# 1P3W_v1p4.net
KiCad netlist of a schematic drawn in EAGLE
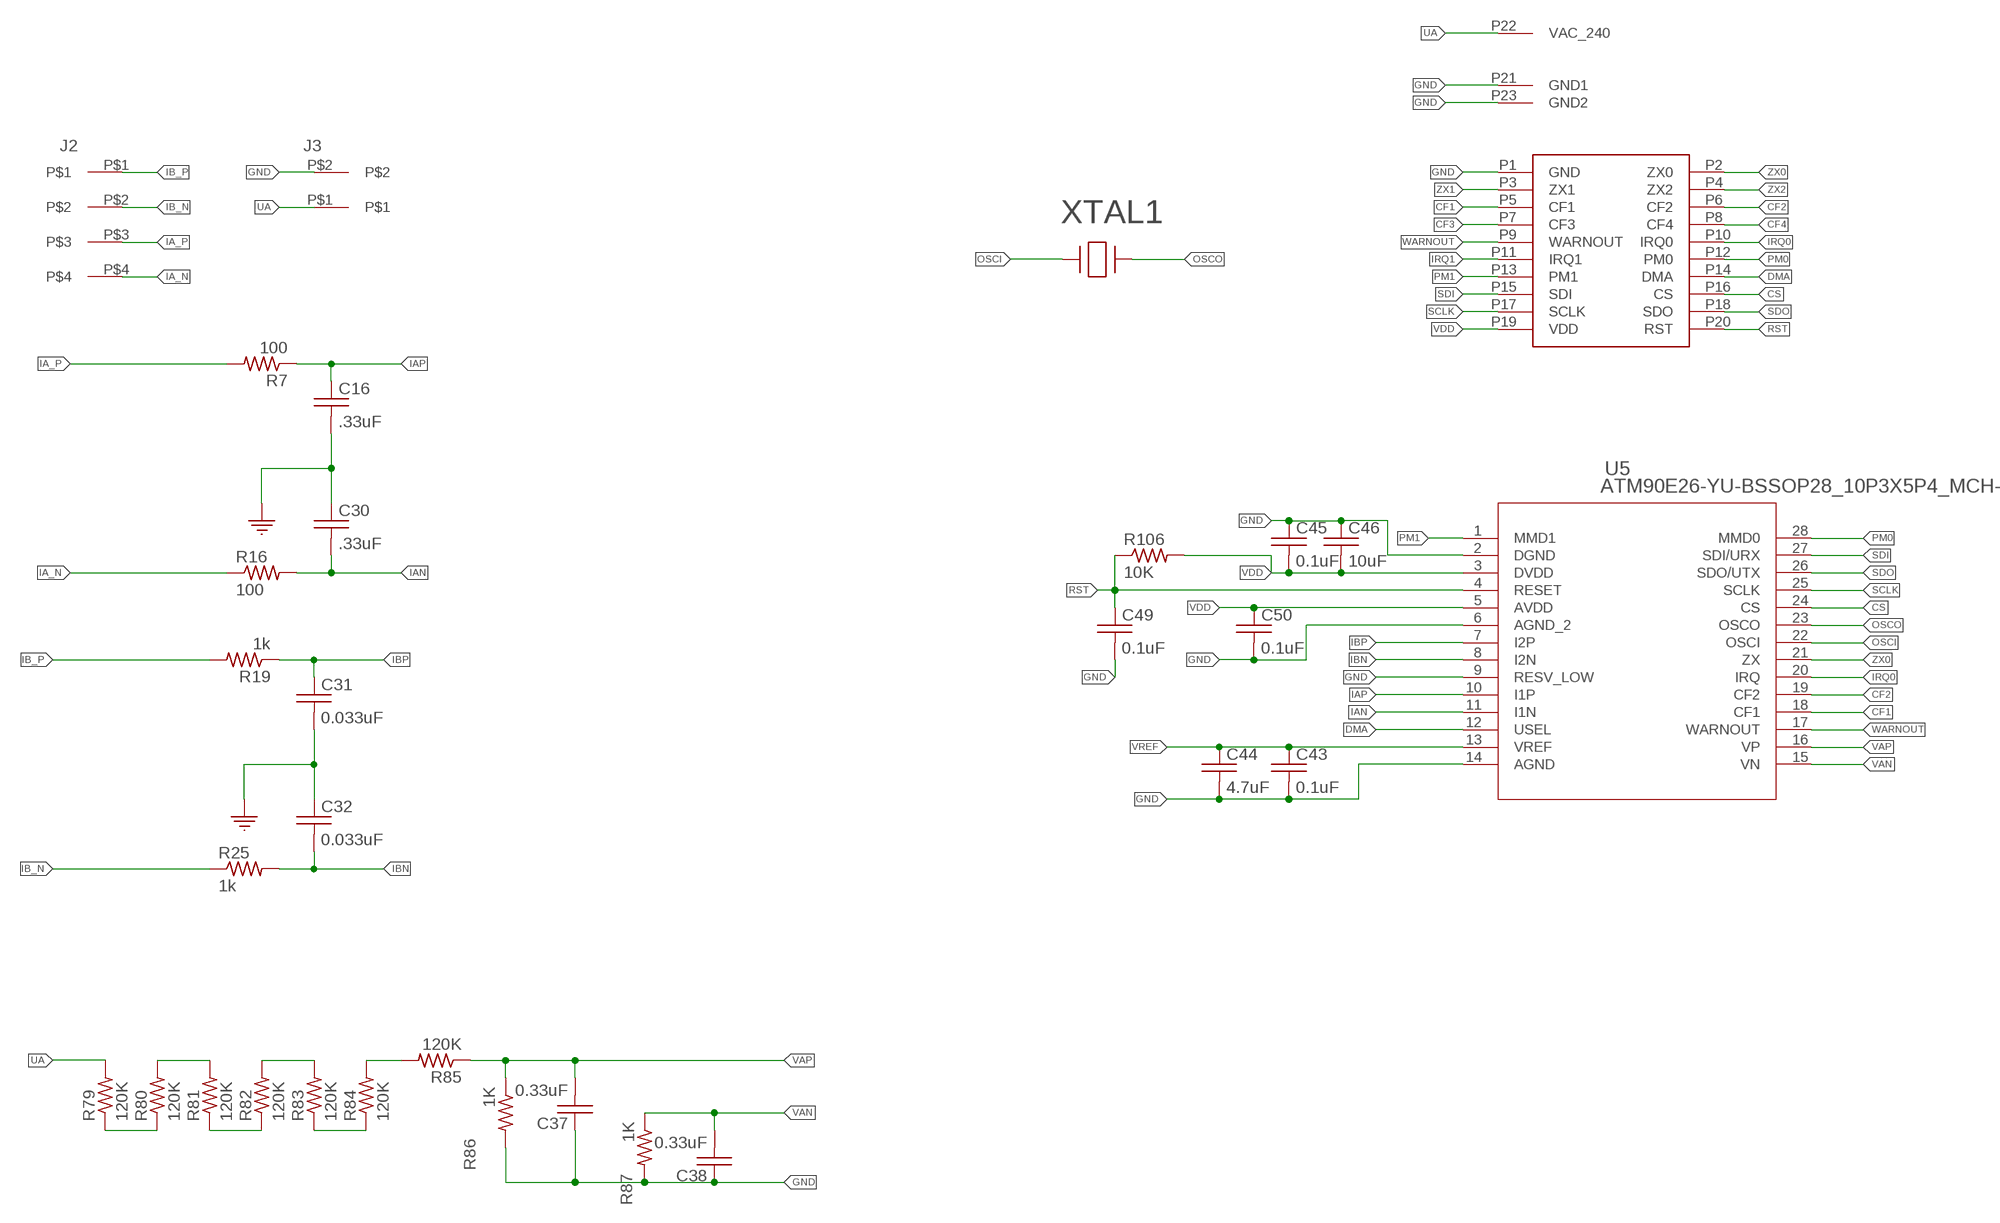
[diagram p0: schematic, sheet 1]

(export (version "E")
  (design (tool "Eeschema 10.0.6"))
  (components
    (comp (ref "C16")
      (value ".33uF")
      (footprint "eagle-import:0402")
      (libsource (lib "eagle-import") (part "C_0402"))
    )
    (comp (ref "C30")
      (value ".33uF")
      (footprint "eagle-import:0402")
      (libsource (lib "eagle-import") (part "C_0402"))
    )
    (comp (ref "C31")
      (value "0.033uF")
      (footprint "eagle-import:0402")
      (libsource (lib "eagle-import") (part "C_0402"))
    )
    (comp (ref "C32")
      (value "0.033uF")
      (footprint "eagle-import:0402")
      (libsource (lib "eagle-import") (part "C_0402"))
    )
    (comp (ref "C37")
      (value "0.33uF")
      (footprint "eagle-import:0402")
      (libsource (lib "eagle-import") (part "C_0402"))
    )
    (comp (ref "C38")
      (value "0.33uF")
      (footprint "eagle-import:0402")
      (libsource (lib "eagle-import") (part "C_0402"))
    )
    (comp (ref "C43")
      (value "0.1uF")
      (footprint "eagle-import:0402")
      (libsource (lib "eagle-import") (part "C_0402"))
    )
    (comp (ref "C44")
      (value "4.7uF")
      (footprint "eagle-import:0402")
      (libsource (lib "eagle-import") (part "C_0402"))
    )
    (comp (ref "C45")
      (value "0.1uF")
      (footprint "eagle-import:0402")
      (libsource (lib "eagle-import") (part "C_0402"))
    )
    (comp (ref "C46")
      (value "10uF")
      (footprint "eagle-import:0402")
      (libsource (lib "eagle-import") (part "C_0402"))
    )
    (comp (ref "C49")
      (value "0.1uF")
      (footprint "eagle-import:0402")
      (libsource (lib "eagle-import") (part "C_0402"))
    )
    (comp (ref "C50")
      (value "0.1uF")
      (footprint "eagle-import:0402")
      (libsource (lib "eagle-import") (part "C_0402"))
    )
    (comp (ref "J2")
      (value "3.81MM_1_X_4_RT_ANGLE_PLUG_HEADER")
      (footprint "eagle-import:1X4_3.81MM_PITCH")
      (libsource (lib "eagle-import") (part "3.81MM_1_X_4_RT_ANGLE_PLUG_HEADER"))
    )
    (comp (ref "J3")
      (value "3.81MM_1_X_2_RT_ANGLE_PLUG_HEADER")
      (footprint "eagle-import:2_3.81MM_PITCH")
      (libsource (lib "eagle-import") (part "3.81MM_1_X_2_RT_ANGLE_PLUG_HEADER"))
    )
    (comp (ref "R7")
      (value "100")
      (footprint "eagle-import:0402")
      (libsource (lib "eagle-import") (part "R_0402"))
    )
    (comp (ref "R16")
      (value "100")
      (footprint "eagle-import:0402")
      (libsource (lib "eagle-import") (part "R_0402"))
    )
    (comp (ref "R19")
      (value "1k")
      (footprint "eagle-import:0402")
      (libsource (lib "eagle-import") (part "R_0402"))
    )
    (comp (ref "R25")
      (value "1k")
      (footprint "eagle-import:0402")
      (libsource (lib "eagle-import") (part "R_0402"))
    )
    (comp (ref "R79")
      (value "120K")
      (footprint "eagle-import:0402")
      (libsource (lib "eagle-import") (part "R_0402"))
    )
    (comp (ref "R80")
      (value "120K")
      (footprint "eagle-import:0402")
      (libsource (lib "eagle-import") (part "R_0402"))
    )
    (comp (ref "R81")
      (value "120K")
      (footprint "eagle-import:0402")
      (libsource (lib "eagle-import") (part "R_0402"))
    )
    (comp (ref "R82")
      (value "120K")
      (footprint "eagle-import:0402")
      (libsource (lib "eagle-import") (part "R_0402"))
    )
    (comp (ref "R83")
      (value "120K")
      (footprint "eagle-import:0402")
      (libsource (lib "eagle-import") (part "R_0402"))
    )
    (comp (ref "R84")
      (value "120K")
      (footprint "eagle-import:0402")
      (libsource (lib "eagle-import") (part "R_0402"))
    )
    (comp (ref "R85")
      (value "120K")
      (footprint "eagle-import:0402")
      (libsource (lib "eagle-import") (part "R_0402"))
    )
    (comp (ref "R86")
      (value "1K")
      (footprint "eagle-import:0402")
      (libsource (lib "eagle-import") (part "R_0402"))
    )
    (comp (ref "R87")
      (value "1K")
      (footprint "eagle-import:0402")
      (libsource (lib "eagle-import") (part "R_0402"))
    )
    (comp (ref "R106")
      (value "10K")
      (footprint "eagle-import:0402")
      (libsource (lib "eagle-import") (part "R_0402"))
    )
    (comp (ref "U$1")
      (value "METER_BASE")
      (footprint "eagle-import:METER_BASE")
      (libsource (lib "eagle-import") (part "METER_BASE"))
    )
    (comp (ref "U5")
      (value "ATM90E26-YU-BSSOP28_10P3X5P4_MCH-M")
      (footprint "eagle-import:SSOP28_10P3X5P4_MCH-M")
      (fields
        (field (name "MANUFACTURER_PART_NUMBER") "ATM90E26-YU-B")
        (field (name "COPYRIGHT") "Copyright (C) 2018 Accelerated Designs. All rights reserved")
      )
      (libsource (lib "eagle-import") (part "ATM90E26-YU-BSSOP28_10P3X5P4_MCH-M"))
    )
    (comp (ref "XTAL1")
      (value "ABLS-8.192MHZ-B2-TXTAL_HC/49US_ABLS_ABR-M")
      (footprint "eagle-import:XTAL_HC_49US_ABLS_ABR-M")
      (fields
        (field (name "MANUFACTURER_PART_NUMBER") "ABLS-8.192MHZ-B2-T")
        (field (name "COPYRIGHT") "Copyright (C) 2018 Accelerated Designs. All rights reserved")
      )
      (libsource (lib "eagle-import") (part "ABLS-8.192MHZ-B2-TXTAL_HC/49US_ABLS_ABR-M"))
    )
  )
  (nets
    (net (code "1") (name "CF1") (class "Default")
      (node (ref "U$1") (pin "P5") (pinfunction "CF1_P5") (pintype "bidirectional"))
      (node (ref "U5") (pin "18") (pinfunction "CF1_18") (pintype "bidirectional"))
    )
    (net (code "2") (name "CF2") (class "Default")
      (node (ref "U$1") (pin "P6") (pinfunction "CF2_P6") (pintype "bidirectional"))
      (node (ref "U5") (pin "19") (pinfunction "CF2_19") (pintype "bidirectional"))
    )
    (net (code "3") (name "CF3") (class "Default")
      (node (ref "U$1") (pin "P7") (pinfunction "CF3_P7") (pintype "bidirectional"))
    )
    (net (code "4") (name "CF4") (class "Default")
      (node (ref "U$1") (pin "P8") (pinfunction "CF4_P8") (pintype "bidirectional"))
    )
    (net (code "5") (name "CS") (class "Default")
      (node (ref "U$1") (pin "P16") (pinfunction "CS_P16") (pintype "bidirectional"))
      (node (ref "U5") (pin "24") (pinfunction "CS_24") (pintype "passive"))
    )
    (net (code "6") (name "DMA") (class "Default")
      (node (ref "U$1") (pin "P14") (pinfunction "DMA_P14") (pintype "bidirectional"))
      (node (ref "U5") (pin "12") (pinfunction "USEL_12") (pintype "passive"))
    )
    (net (code "7") (name "GND") (class "Default")
      (node (ref "C16") (pin "P$2") (pinfunction "2_P$2") (pintype "passive"))
      (node (ref "C30") (pin "P$1") (pinfunction "1_P$1") (pintype "passive"))
      (node (ref "C31") (pin "P$2") (pinfunction "2_P$2") (pintype "passive"))
      (node (ref "C32") (pin "P$1") (pinfunction "1_P$1") (pintype "passive"))
      (node (ref "C37") (pin "P$1") (pinfunction "1_P$1") (pintype "passive"))
      (node (ref "C38") (pin "P$1") (pinfunction "1_P$1") (pintype "passive"))
      (node (ref "C43") (pin "P$2") (pinfunction "2_P$2") (pintype "passive"))
      (node (ref "C44") (pin "P$2") (pinfunction "2_P$2") (pintype "passive"))
      (node (ref "C45") (pin "P$1") (pinfunction "1_P$1") (pintype "passive"))
      (node (ref "C46") (pin "P$1") (pinfunction "1_P$1") (pintype "passive"))
      (node (ref "C49") (pin "P$2") (pinfunction "2_P$2") (pintype "passive"))
      (node (ref "C50") (pin "P$2") (pinfunction "2_P$2") (pintype "passive"))
      (node (ref "J3") (pin "P$2") (pinfunction "P$2_P$2") (pintype "bidirectional"))
      (node (ref "R86") (pin "P$2") (pinfunction "2_P$2") (pintype "passive"))
      (node (ref "R87") (pin "P$2") (pinfunction "2_P$2") (pintype "passive"))
      (node (ref "U$1") (pin "P1") (pinfunction "GND_P1") (pintype "bidirectional"))
      (node (ref "U$1") (pin "P21") (pinfunction "GND1_P21") (pintype "bidirectional"))
      (node (ref "U$1") (pin "P23") (pinfunction "GND2_P23") (pintype "bidirectional"))
      (node (ref "U5") (pin "14") (pinfunction "AGND_14") (pintype "passive"))
      (node (ref "U5") (pin "2") (pinfunction "DGND_2") (pintype "passive"))
      (node (ref "U5") (pin "6") (pinfunction "AGND_2_6") (pintype "passive"))
      (node (ref "U5") (pin "9") (pinfunction "RESV_LOW_9") (pintype "passive"))
    )
    (net (code "8") (name "IAN") (class "Default")
      (node (ref "C30") (pin "P$2") (pinfunction "2_P$2") (pintype "passive"))
      (node (ref "R16") (pin "P$2") (pinfunction "2_P$2") (pintype "passive"))
      (node (ref "U5") (pin "11") (pinfunction "I1N_11") (pintype "bidirectional"))
    )
    (net (code "9") (name "IAP") (class "Default")
      (node (ref "C16") (pin "P$1") (pinfunction "1_P$1") (pintype "passive"))
      (node (ref "R7") (pin "P$1") (pinfunction "1_P$1") (pintype "passive"))
      (node (ref "U5") (pin "10") (pinfunction "I1P_10") (pintype "bidirectional"))
    )
    (net (code "10") (name "IA_N") (class "Default")
      (node (ref "J2") (pin "P$4") (pinfunction "P$4_P$4") (pintype "bidirectional"))
      (node (ref "R16") (pin "P$1") (pinfunction "1_P$1") (pintype "passive"))
    )
    (net (code "11") (name "IA_P") (class "Default")
      (node (ref "J2") (pin "P$3") (pinfunction "P$3_P$3") (pintype "bidirectional"))
      (node (ref "R7") (pin "P$2") (pinfunction "2_P$2") (pintype "passive"))
    )
    (net (code "12") (name "IBN") (class "Default")
      (node (ref "C32") (pin "P$2") (pinfunction "2_P$2") (pintype "passive"))
      (node (ref "R25") (pin "P$2") (pinfunction "2_P$2") (pintype "passive"))
      (node (ref "U5") (pin "8") (pinfunction "I2N_8") (pintype "bidirectional"))
    )
    (net (code "13") (name "IBP") (class "Default")
      (node (ref "C31") (pin "P$1") (pinfunction "1_P$1") (pintype "passive"))
      (node (ref "R19") (pin "P$1") (pinfunction "1_P$1") (pintype "passive"))
      (node (ref "U5") (pin "7") (pinfunction "I2P_7") (pintype "bidirectional"))
    )
    (net (code "14") (name "IB_N") (class "Default")
      (node (ref "J2") (pin "P$2") (pinfunction "P$2_P$2") (pintype "bidirectional"))
      (node (ref "R25") (pin "P$1") (pinfunction "1_P$1") (pintype "passive"))
    )
    (net (code "15") (name "IB_P") (class "Default")
      (node (ref "J2") (pin "P$1") (pinfunction "P$1_P$1") (pintype "bidirectional"))
      (node (ref "R19") (pin "P$2") (pinfunction "2_P$2") (pintype "passive"))
    )
    (net (code "16") (name "IRQ0") (class "Default")
      (node (ref "U$1") (pin "P10") (pinfunction "IRQ0_P10") (pintype "bidirectional"))
      (node (ref "U5") (pin "20") (pinfunction "IRQ_20") (pintype "passive"))
    )
    (net (code "17") (name "IRQ1") (class "Default")
      (node (ref "U$1") (pin "P11") (pinfunction "IRQ1_P11") (pintype "bidirectional"))
    )
    (net (code "18") (name "Net-(R79-1)") (class "Default")
      (node (ref "R79") (pin "P$1") (pinfunction "1_P$1") (pintype "passive"))
      (node (ref "R80") (pin "P$1") (pinfunction "1_P$1") (pintype "passive"))
    )
    (net (code "19") (name "Net-(R80-2)") (class "Default")
      (node (ref "R80") (pin "P$2") (pinfunction "2_P$2") (pintype "passive"))
      (node (ref "R81") (pin "P$2") (pinfunction "2_P$2") (pintype "passive"))
    )
    (net (code "20") (name "Net-(R81-1)") (class "Default")
      (node (ref "R81") (pin "P$1") (pinfunction "1_P$1") (pintype "passive"))
      (node (ref "R82") (pin "P$1") (pinfunction "1_P$1") (pintype "passive"))
    )
    (net (code "21") (name "Net-(R82-2)") (class "Default")
      (node (ref "R82") (pin "P$2") (pinfunction "2_P$2") (pintype "passive"))
      (node (ref "R83") (pin "P$2") (pinfunction "2_P$2") (pintype "passive"))
    )
    (net (code "22") (name "Net-(R83-1)") (class "Default")
      (node (ref "R83") (pin "P$1") (pinfunction "1_P$1") (pintype "passive"))
      (node (ref "R84") (pin "P$1") (pinfunction "1_P$1") (pintype "passive"))
    )
    (net (code "23") (name "Net-(R84-2)") (class "Default")
      (node (ref "R84") (pin "P$2") (pinfunction "2_P$2") (pintype "passive"))
      (node (ref "R85") (pin "P$2") (pinfunction "2_P$2") (pintype "passive"))
    )
    (net (code "24") (name "OSCI") (class "Default")
      (node (ref "U5") (pin "22") (pinfunction "OSCI_22") (pintype "passive"))
      (node (ref "XTAL1") (pin "1") (pinfunction "1_1") (pintype "passive"))
    )
    (net (code "25") (name "OSCO") (class "Default")
      (node (ref "U5") (pin "23") (pinfunction "OSCO_23") (pintype "passive"))
      (node (ref "XTAL1") (pin "2") (pinfunction "2_2") (pintype "passive"))
    )
    (net (code "26") (name "PM0") (class "Default")
      (node (ref "U$1") (pin "P12") (pinfunction "PM0_P12") (pintype "bidirectional"))
      (node (ref "U5") (pin "28") (pinfunction "MMD0_28") (pintype "bidirectional"))
    )
    (net (code "27") (name "PM1") (class "Default")
      (node (ref "U$1") (pin "P13") (pinfunction "PM1_P13") (pintype "bidirectional"))
      (node (ref "U5") (pin "1") (pinfunction "MMD1_1") (pintype "bidirectional"))
    )
    (net (code "28") (name "RST") (class "Default")
      (node (ref "C49") (pin "P$1") (pinfunction "1_P$1") (pintype "passive"))
      (node (ref "R106") (pin "P$1") (pinfunction "1_P$1") (pintype "passive"))
      (node (ref "U$1") (pin "P20") (pinfunction "RST_P20") (pintype "bidirectional"))
      (node (ref "U5") (pin "4") (pinfunction "RESET_4") (pintype "passive"))
    )
    (net (code "29") (name "SCLK") (class "Default")
      (node (ref "U$1") (pin "P17") (pinfunction "SCLK_P17") (pintype "bidirectional"))
      (node (ref "U5") (pin "25") (pinfunction "SCLK_25") (pintype "passive"))
    )
    (net (code "30") (name "SDI") (class "Default")
      (node (ref "U$1") (pin "P15") (pinfunction "SDI_P15") (pintype "bidirectional"))
      (node (ref "U5") (pin "27") (pinfunction "SDI/URX_27") (pintype "passive"))
    )
    (net (code "31") (name "SDO") (class "Default")
      (node (ref "U$1") (pin "P18") (pinfunction "SDO_P18") (pintype "bidirectional"))
      (node (ref "U5") (pin "26") (pinfunction "SDO/UTX_26") (pintype "passive"))
    )
    (net (code "32") (name "UA") (class "Default")
      (node (ref "J3") (pin "P$1") (pinfunction "P$1_P$1") (pintype "bidirectional"))
      (node (ref "R79") (pin "P$2") (pinfunction "2_P$2") (pintype "passive"))
      (node (ref "U$1") (pin "P22") (pinfunction "VAC_240_P22") (pintype "bidirectional"))
    )
    (net (code "33") (name "VAN") (class "Default")
      (node (ref "C38") (pin "P$2") (pinfunction "2_P$2") (pintype "passive"))
      (node (ref "R87") (pin "P$1") (pinfunction "1_P$1") (pintype "passive"))
      (node (ref "U5") (pin "15") (pinfunction "VN_15") (pintype "passive"))
    )
    (net (code "34") (name "VAP") (class "Default")
      (node (ref "C37") (pin "P$2") (pinfunction "2_P$2") (pintype "passive"))
      (node (ref "R85") (pin "P$1") (pinfunction "1_P$1") (pintype "passive"))
      (node (ref "R86") (pin "P$1") (pinfunction "1_P$1") (pintype "passive"))
      (node (ref "U5") (pin "16") (pinfunction "VP_16") (pintype "passive"))
    )
    (net (code "35") (name "VDD") (class "Default")
      (node (ref "C45") (pin "P$2") (pinfunction "2_P$2") (pintype "passive"))
      (node (ref "C46") (pin "P$2") (pinfunction "2_P$2") (pintype "passive"))
      (node (ref "C50") (pin "P$1") (pinfunction "1_P$1") (pintype "passive"))
      (node (ref "R106") (pin "P$2") (pinfunction "2_P$2") (pintype "passive"))
      (node (ref "U$1") (pin "P19") (pinfunction "VDD_P19") (pintype "bidirectional"))
      (node (ref "U5") (pin "3") (pinfunction "DVDD_3") (pintype "power_in"))
      (node (ref "U5") (pin "5") (pinfunction "AVDD_5") (pintype "power_in"))
    )
    (net (code "36") (name "VREF") (class "Default")
      (node (ref "C43") (pin "P$1") (pinfunction "1_P$1") (pintype "passive"))
      (node (ref "C44") (pin "P$1") (pinfunction "1_P$1") (pintype "passive"))
      (node (ref "U5") (pin "13") (pinfunction "VREF_13") (pintype "power_in"))
    )
    (net (code "37") (name "WARNOUT") (class "Default")
      (node (ref "U$1") (pin "P9") (pinfunction "WARNOUT_P9") (pintype "bidirectional"))
      (node (ref "U5") (pin "17") (pinfunction "WARNOUT_17") (pintype "output"))
    )
    (net (code "38") (name "ZX0") (class "Default")
      (node (ref "U$1") (pin "P2") (pinfunction "ZX0_P2") (pintype "bidirectional"))
      (node (ref "U5") (pin "21") (pinfunction "ZX_21") (pintype "passive"))
    )
    (net (code "39") (name "ZX1") (class "Default")
      (node (ref "U$1") (pin "P3") (pinfunction "ZX1_P3") (pintype "bidirectional"))
    )
    (net (code "40") (name "ZX2") (class "Default")
      (node (ref "U$1") (pin "P4") (pinfunction "ZX2_P4") (pintype "bidirectional"))
    )
  )
)
